# BootFlash_SPI.net
KiCad netlist of a schematic drawn in Altium Designer
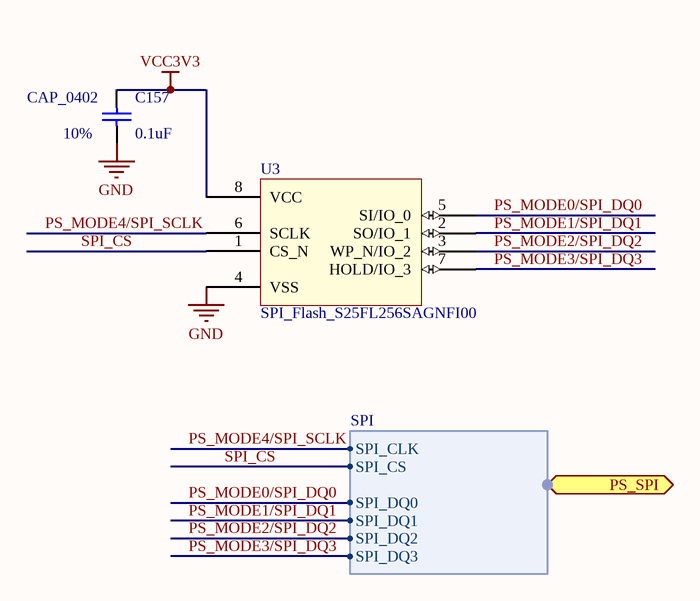
[diagram p0: BootFlash_SPI.SchDoc]

(export (version "E")
  (design (tool "Eeschema 10.0.6"))
  (components
    (comp (ref "C157")
      (value "CAP_0402")
      (footprint "CAPC0402(1005)60_N")
      (description "0.1uf, ceramic, 10%, 6.3V, X5R, 0402")
      (fields
        (field (name "ALTIUM_VALUE") "0.1uF")
        (field (name "TOLERANCE") "10%")
        (field (name "PART NUMBER") "C1005X5R0J104K")
        (field (name "MANUFACTURER") "TDK Corporation")
      )
      (libsource (lib "COMRAD_Database") (part "CAP_0402"))
    )
    (comp (ref "U3")
      (value "SPI_Flash_S25FL256SAGNFI00")
      (footprint "SPI_Flash_S25FL256SAGNFI00_WSON-8")
      (description "S25FL256SAGMFI00, Serial Flash Memory, 256Mbit, Low Voltage, 104MHz SPI Bus Interface, SOIC16 WIDE")
      (fields (field (name "PART NUMBER") "S25FL256SAGNFI001") (field (name "MANUFACTURER") "Spansion"))
      (libsource (lib "COMRAD_Database") (part "SPI_Flash_S25FL256SAGNFI00"))
    )
  )
  (nets
    (net (code "2") (name "/PS_MODE0{slash}SPI_DQ0") (class "Default")
      (node (ref "U3") (pin "5") (pinfunction "SI/IO_0_5") (pintype "bidirectional"))
    )
    (net (code "3") (name "/PS_MODE1{slash}SPI_DQ1") (class "Default")
      (node (ref "U3") (pin "2") (pinfunction "SO/IO_1_2") (pintype "bidirectional"))
    )
    (net (code "4") (name "/PS_MODE2{slash}SPI_DQ2") (class "Default")
      (node (ref "U3") (pin "3") (pinfunction "WP_N/IO_2_3") (pintype "bidirectional"))
    )
    (net (code "5") (name "/PS_MODE3{slash}SPI_DQ3") (class "Default")
      (node (ref "U3") (pin "7") (pinfunction "HOLD/IO_3_7") (pintype "bidirectional"))
    )
    (net (code "6") (name "/PS_MODE4{slash}SPI_SCLK") (class "Default")
      (node (ref "U3") (pin "6") (pinfunction "SCLK_6") (pintype "passive"))
    )
    (net (code "7") (name "/SPI_CS") (class "Default")
      (node (ref "U3") (pin "1") (pinfunction "CS_N_1") (pintype "passive"))
    )
    (net (code "9") (name "GND") (class "Default")
      (node (ref "C157") (pin "1") (pinfunction "1_1") (pintype "passive"))
      (node (ref "U3") (pin "4") (pinfunction "VSS_4") (pintype "power_in"))
    )
    (net (code "10") (name "VCC3V3") (class "Default")
      (node (ref "C157") (pin "2") (pinfunction "2_2") (pintype "passive"))
      (node (ref "U3") (pin "8") (pinfunction "VCC_8") (pintype "power_in"))
    )
  )
)
